# CC-S08-V00-Connector.net
KiCad netlist of a schematic drawn in Altium Designer
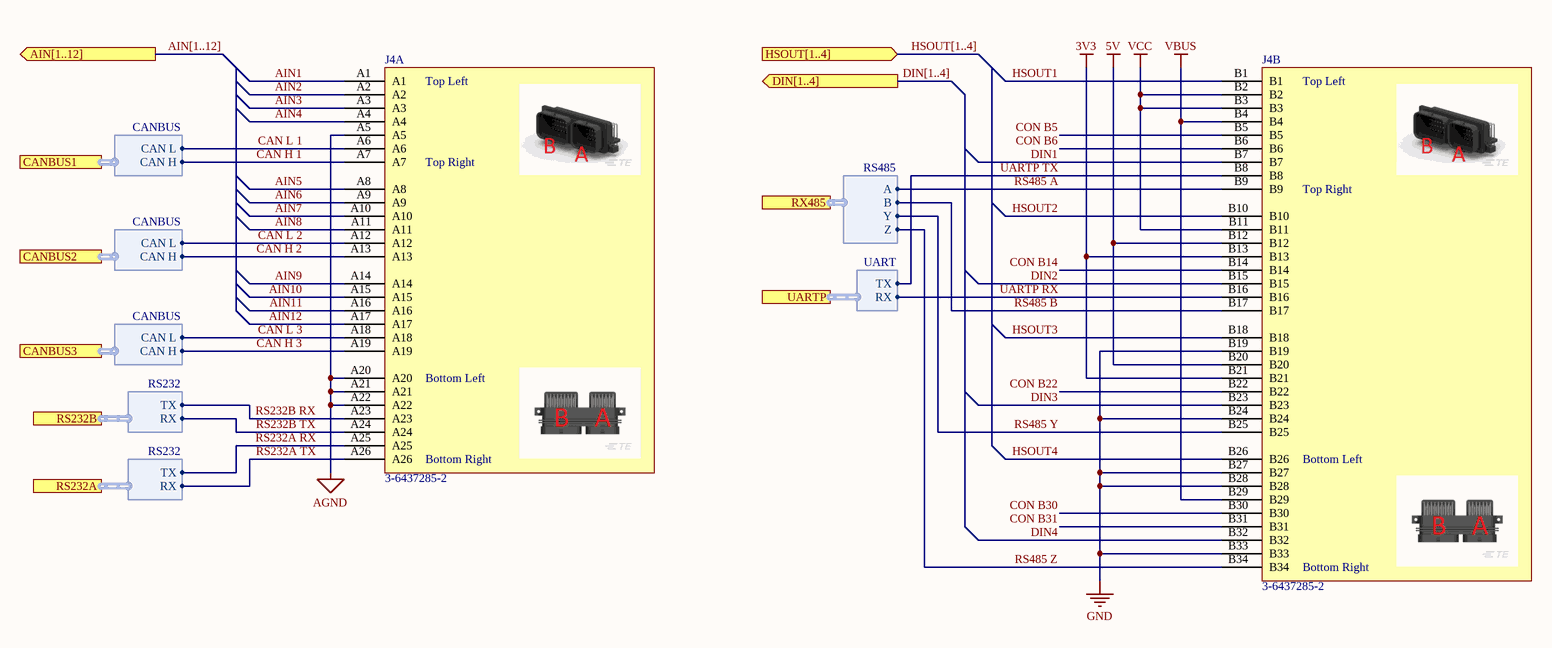
[diagram p0: CC-S08-V00-Connector.SchDoc]

(export (version "E")
  (design (tool "Eeschema 10.0.6"))
  (components
    (comp (ref "J4")
      (value "3-6437285-2")
      (footprint "SUPERSEAL RIGHT 60WAY")
      (description "Connector Header Through Hole, Right Angle 60 position 0.118\" (3.00mm)")
      (libsource (lib "QUTMS_SupersealPCB") (part "3-6437285-2"))
    )
  )
  (nets
    (net (code "5") (name "/AIN1") (class "Default")
      (node (ref "J4") (pin "A1") (pinfunction "A1_A1") (pintype "passive"))
    )
    (net (code "6") (name "/AIN2") (class "Default")
      (node (ref "J4") (pin "A2") (pinfunction "A2_A2") (pintype "passive"))
    )
    (net (code "7") (name "/AIN3") (class "Default")
      (node (ref "J4") (pin "A3") (pinfunction "A3_A3") (pintype "passive"))
    )
    (net (code "8") (name "/AIN4") (class "Default")
      (node (ref "J4") (pin "A4") (pinfunction "A4_A4") (pintype "passive"))
    )
    (net (code "9") (name "/AIN5") (class "Default")
      (node (ref "J4") (pin "A8") (pinfunction "A8_A8") (pintype "passive"))
    )
    (net (code "10") (name "/AIN6") (class "Default")
      (node (ref "J4") (pin "A9") (pinfunction "A9_A9") (pintype "passive"))
    )
    (net (code "11") (name "/AIN7") (class "Default")
      (node (ref "J4") (pin "A10") (pinfunction "A10_A10") (pintype "passive"))
    )
    (net (code "12") (name "/AIN8") (class "Default")
      (node (ref "J4") (pin "A11") (pinfunction "A11_A11") (pintype "passive"))
    )
    (net (code "13") (name "/AIN9") (class "Default")
      (node (ref "J4") (pin "A14") (pinfunction "A14_A14") (pintype "passive"))
    )
    (net (code "14") (name "/AIN10") (class "Default")
      (node (ref "J4") (pin "A15") (pinfunction "A15_A15") (pintype "passive"))
    )
    (net (code "15") (name "/AIN11") (class "Default")
      (node (ref "J4") (pin "A16") (pinfunction "A16_A16") (pintype "passive"))
    )
    (net (code "16") (name "/AIN12") (class "Default")
      (node (ref "J4") (pin "A17") (pinfunction "A17_A17") (pintype "passive"))
    )
    (net (code "18") (name "/CAN H 1") (class "Default")
      (node (ref "J4") (pin "A7") (pinfunction "A7_A7") (pintype "passive"))
    )
    (net (code "19") (name "/CAN H 2") (class "Default")
      (node (ref "J4") (pin "A13") (pinfunction "A13_A13") (pintype "passive"))
    )
    (net (code "20") (name "/CAN H 3") (class "Default")
      (node (ref "J4") (pin "A19") (pinfunction "A19_A19") (pintype "passive"))
    )
    (net (code "21") (name "/CAN L 1") (class "Default")
      (node (ref "J4") (pin "A6") (pinfunction "A6_A6") (pintype "passive"))
    )
    (net (code "22") (name "/CAN L 2") (class "Default")
      (node (ref "J4") (pin "A12") (pinfunction "A12_A12") (pintype "passive"))
    )
    (net (code "23") (name "/CAN L 3") (class "Default")
      (node (ref "J4") (pin "A18") (pinfunction "A18_A18") (pintype "passive"))
    )
    (net (code "24") (name "/CON B5") (class "Default")
      (node (ref "J4") (pin "B5") (pinfunction "B5_B5") (pintype "passive"))
    )
    (net (code "25") (name "/CON B6") (class "Default")
      (node (ref "J4") (pin "B6") (pinfunction "B6_B6") (pintype "passive"))
    )
    (net (code "26") (name "/CON B14") (class "Default")
      (node (ref "J4") (pin "B14") (pinfunction "B14_B14") (pintype "passive"))
    )
    (net (code "27") (name "/CON B22") (class "Default")
      (node (ref "J4") (pin "B22") (pinfunction "B22_B22") (pintype "passive"))
    )
    (net (code "28") (name "/CON B30") (class "Default")
      (node (ref "J4") (pin "B30") (pinfunction "B30_B30") (pintype "passive"))
    )
    (net (code "29") (name "/CON B31") (class "Default")
      (node (ref "J4") (pin "B31") (pinfunction "B31_B31") (pintype "passive"))
    )
    (net (code "30") (name "/DIN1") (class "Default")
      (node (ref "J4") (pin "B7") (pinfunction "B7_B7") (pintype "passive"))
    )
    (net (code "31") (name "/DIN2") (class "Default")
      (node (ref "J4") (pin "B15") (pinfunction "B15_B15") (pintype "passive"))
    )
    (net (code "32") (name "/DIN3") (class "Default")
      (node (ref "J4") (pin "B23") (pinfunction "B23_B23") (pintype "passive"))
    )
    (net (code "33") (name "/DIN4") (class "Default")
      (node (ref "J4") (pin "B32") (pinfunction "B32_B32") (pintype "passive"))
    )
    (net (code "35") (name "/HSOUT1") (class "Default")
      (node (ref "J4") (pin "B1") (pinfunction "B1_B1") (pintype "passive"))
    )
    (net (code "36") (name "/HSOUT2") (class "Default")
      (node (ref "J4") (pin "B10") (pinfunction "B10_B10") (pintype "passive"))
    )
    (net (code "37") (name "/HSOUT3") (class "Default")
      (node (ref "J4") (pin "B18") (pinfunction "B18_B18") (pintype "passive"))
    )
    (net (code "38") (name "/HSOUT4") (class "Default")
      (node (ref "J4") (pin "B26") (pinfunction "B26_B26") (pintype "passive"))
    )
    (net (code "40") (name "/RS232A RX") (class "Default")
      (node (ref "J4") (pin "A25") (pinfunction "A25_A25") (pintype "passive"))
    )
    (net (code "41") (name "/RS232A TX") (class "Default")
      (node (ref "J4") (pin "A26") (pinfunction "A26_A26") (pintype "passive"))
    )
    (net (code "42") (name "/RS232B RX") (class "Default")
      (node (ref "J4") (pin "A23") (pinfunction "A23_A23") (pintype "passive"))
    )
    (net (code "43") (name "/RS232B TX") (class "Default")
      (node (ref "J4") (pin "A24") (pinfunction "A24_A24") (pintype "passive"))
    )
    (net (code "44") (name "/RS485 A") (class "Default")
      (node (ref "J4") (pin "B9") (pinfunction "B9_B9") (pintype "passive"))
    )
    (net (code "45") (name "/RS485 B") (class "Default")
      (node (ref "J4") (pin "B17") (pinfunction "B17_B17") (pintype "passive"))
    )
    (net (code "46") (name "/RS485 Y") (class "Default")
      (node (ref "J4") (pin "B25") (pinfunction "B25_B25") (pintype "passive"))
    )
    (net (code "47") (name "/RS485 Z") (class "Default")
      (node (ref "J4") (pin "B34") (pinfunction "B34_B34") (pintype "passive"))
    )
    (net (code "48") (name "/UARTP RX") (class "Default")
      (node (ref "J4") (pin "B16") (pinfunction "B16_B16") (pintype "passive"))
    )
    (net (code "49") (name "/UARTP TX") (class "Default")
      (node (ref "J4") (pin "B8") (pinfunction "B8_B8") (pintype "passive"))
    )
    (net (code "54") (name "3V3") (class "Default")
      (node (ref "J4") (pin "B13") (pinfunction "B13_B13") (pintype "passive"))
      (node (ref "J4") (pin "B21") (pinfunction "B21_B21") (pintype "passive"))
    )
    (net (code "55") (name "5V") (class "Default")
      (node (ref "J4") (pin "B12") (pinfunction "B12_B12") (pintype "passive"))
      (node (ref "J4") (pin "B20") (pinfunction "B20_B20") (pintype "passive"))
    )
    (net (code "56") (name "AGND") (class "Default")
      (node (ref "J4") (pin "A20") (pinfunction "A20_A20") (pintype "passive"))
      (node (ref "J4") (pin "A21") (pinfunction "A21_A21") (pintype "passive"))
      (node (ref "J4") (pin "A22") (pinfunction "A22_A22") (pintype "passive"))
      (node (ref "J4") (pin "A5") (pinfunction "A5_A5") (pintype "passive"))
    )
    (net (code "57") (name "GND") (class "Default")
      (node (ref "J4") (pin "B19") (pinfunction "B19_B19") (pintype "passive"))
      (node (ref "J4") (pin "B24") (pinfunction "B24_B24") (pintype "passive"))
      (node (ref "J4") (pin "B27") (pinfunction "B27_B27") (pintype "passive"))
      (node (ref "J4") (pin "B28") (pinfunction "B28_B28") (pintype "passive"))
      (node (ref "J4") (pin "B33") (pinfunction "B33_B33") (pintype "passive"))
    )
    (net (code "58") (name "VBUS") (class "Default")
      (node (ref "J4") (pin "B29") (pinfunction "B29_B29") (pintype "passive"))
      (node (ref "J4") (pin "B4") (pinfunction "B4_B4") (pintype "passive"))
    )
    (net (code "59") (name "VCC") (class "Default")
      (node (ref "J4") (pin "B11") (pinfunction "B11_B11") (pintype "passive"))
      (node (ref "J4") (pin "B2") (pinfunction "B2_B2") (pintype "passive"))
      (node (ref "J4") (pin "B3") (pinfunction "B3_B3") (pintype "passive"))
    )
  )
)
